# PICKIT4-adaptor3.net
KiCad netlist of a schematic drawn in EAGLE
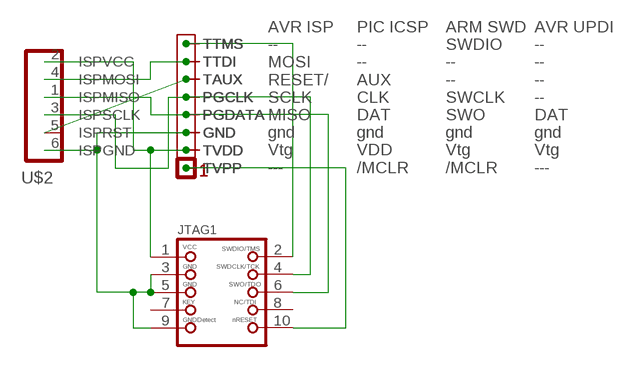
[diagram p0: schematic, sheet 1]

(export (version "E")
  (design (tool "Eeschema 10.0.6"))
  (components
    (comp (ref "JTAG1")
      (value "JTAG-CORTEXM3")
      (footprint "eagle-import:2X05_1.27MM_SMT")
      (libsource (lib "eagle-import") (part "JTAG-CORTEXM3"))
    )
    (comp (ref "U$1")
      (value "PICKIT4PINHDR")
      (footprint "eagle-import:PINHEAD1X8")
      (libsource (lib "eagle-import") (part "PICKIT4PINHDR"))
    )
    (comp (ref "U$2")
      (value "AVR-ISP")
      (footprint "eagle-import:6PINS")
      (libsource (lib "eagle-import") (part "AVR-ISP"))
    )
    (comp (ref "U$3")
      (value "PICKIT4PINHDR")
      (footprint "eagle-import:PINHEAD1X8")
      (libsource (lib "eagle-import") (part "PICKIT4PINHDR"))
    )
    (comp (ref "U$4")
      (value "PICKIT4PINHDR")
      (footprint "eagle-import:PINHEAD1X8")
      (libsource (lib "eagle-import") (part "PICKIT4PINHDR"))
    )
  )
  (nets
    (net (code "1") (name "Net-(U$1A-GND)") (class "Default")
      (node (ref "JTAG1") (pin "3") (pinfunction "3_3") (pintype "passive"))
      (node (ref "JTAG1") (pin "5") (pinfunction "5_5") (pintype "passive"))
      (node (ref "JTAG1") (pin "9") (pinfunction "9_9") (pintype "passive"))
      (node (ref "U$1") (pin "P$3") (pinfunction "GND_P$3") (pintype "power_in"))
      (node (ref "U$2") (pin "6") (pinfunction "ISPGND_6") (pintype "power_in"))
      (node (ref "U$3") (pin "P$3") (pinfunction "GND_P$3") (pintype "power_in"))
      (node (ref "U$4") (pin "P$3") (pinfunction "GND_P$3") (pintype "power_in"))
    )
    (net (code "2") (name "Net-(U$1A-PGCLK)") (class "Default")
      (node (ref "JTAG1") (pin "4") (pinfunction "4_4") (pintype "passive"))
      (node (ref "U$1") (pin "P$5") (pinfunction "PGCLK_P$5") (pintype "bidirectional"))
      (node (ref "U$2") (pin "3") (pinfunction "ISPSCLK_3") (pintype "output"))
      (node (ref "U$3") (pin "P$5") (pinfunction "PGCLK_P$5") (pintype "bidirectional"))
      (node (ref "U$4") (pin "P$5") (pinfunction "PGCLK_P$5") (pintype "bidirectional"))
    )
    (net (code "3") (name "Net-(U$1A-PGDATA)") (class "Default")
      (node (ref "JTAG1") (pin "6") (pinfunction "6_6") (pintype "passive"))
      (node (ref "U$1") (pin "P$4") (pinfunction "PGDATA_P$4") (pintype "bidirectional"))
      (node (ref "U$2") (pin "1") (pinfunction "ISPMISO_1") (pintype "input"))
      (node (ref "U$3") (pin "P$4") (pinfunction "PGDATA_P$4") (pintype "bidirectional"))
      (node (ref "U$4") (pin "P$4") (pinfunction "PGDATA_P$4") (pintype "bidirectional"))
    )
    (net (code "4") (name "Net-(U$1A-TAUX)") (class "Default")
      (node (ref "U$1") (pin "P$6") (pinfunction "TAUX_P$6") (pintype "bidirectional"))
      (node (ref "U$2") (pin "5") (pinfunction "ISPRST_5") (pintype "input"))
      (node (ref "U$3") (pin "P$6") (pinfunction "TAUX_P$6") (pintype "bidirectional"))
      (node (ref "U$4") (pin "P$6") (pinfunction "TAUX_P$6") (pintype "bidirectional"))
    )
    (net (code "5") (name "Net-(U$1A-TTDI)") (class "Default")
      (node (ref "U$1") (pin "P$7") (pinfunction "TTDI_P$7") (pintype "bidirectional"))
      (node (ref "U$2") (pin "4") (pinfunction "ISPMOSI_4") (pintype "output"))
      (node (ref "U$3") (pin "P$7") (pinfunction "TTDI_P$7") (pintype "bidirectional"))
      (node (ref "U$4") (pin "P$7") (pinfunction "TTDI_P$7") (pintype "bidirectional"))
    )
    (net (code "6") (name "Net-(U$1A-TTMS)") (class "Default")
      (node (ref "JTAG1") (pin "2") (pinfunction "2_2") (pintype "passive"))
      (node (ref "U$1") (pin "P$8") (pinfunction "TTMS_P$8") (pintype "bidirectional"))
      (node (ref "U$3") (pin "P$8") (pinfunction "TTMS_P$8") (pintype "bidirectional"))
      (node (ref "U$4") (pin "P$8") (pinfunction "TTMS_P$8") (pintype "bidirectional"))
    )
    (net (code "7") (name "Net-(U$1A-TVDD)") (class "Default")
      (node (ref "JTAG1") (pin "1") (pinfunction "1_1") (pintype "passive"))
      (node (ref "U$1") (pin "P$2") (pinfunction "TVDD_P$2") (pintype "bidirectional"))
      (node (ref "U$2") (pin "2") (pinfunction "ISPVCC_2") (pintype "power_in"))
      (node (ref "U$3") (pin "P$2") (pinfunction "TVDD_P$2") (pintype "bidirectional"))
      (node (ref "U$4") (pin "P$2") (pinfunction "TVDD_P$2") (pintype "bidirectional"))
    )
    (net (code "8") (name "Net-(U$1A-TVPP)") (class "Default")
      (node (ref "JTAG1") (pin "10") (pinfunction "10_10") (pintype "passive"))
      (node (ref "U$1") (pin "P$1") (pinfunction "TVPP_P$1") (pintype "bidirectional"))
      (node (ref "U$3") (pin "P$1") (pinfunction "TVPP_P$1") (pintype "bidirectional"))
      (node (ref "U$4") (pin "P$1") (pinfunction "TVPP_P$1") (pintype "bidirectional"))
    )
    (net (code "9") (name "unconnected-(JTAG1-Pad7)") (class "Default")
      (node (ref "JTAG1") (pin "7") (pinfunction "7_7") (pintype "passive"))
    )
    (net (code "10") (name "unconnected-(JTAG1-Pad8)") (class "Default")
      (node (ref "JTAG1") (pin "8") (pinfunction "8_8") (pintype "passive"))
    )
  )
)
